# Connector-Section.net
KiCad netlist of a schematic drawn in Altium Designer
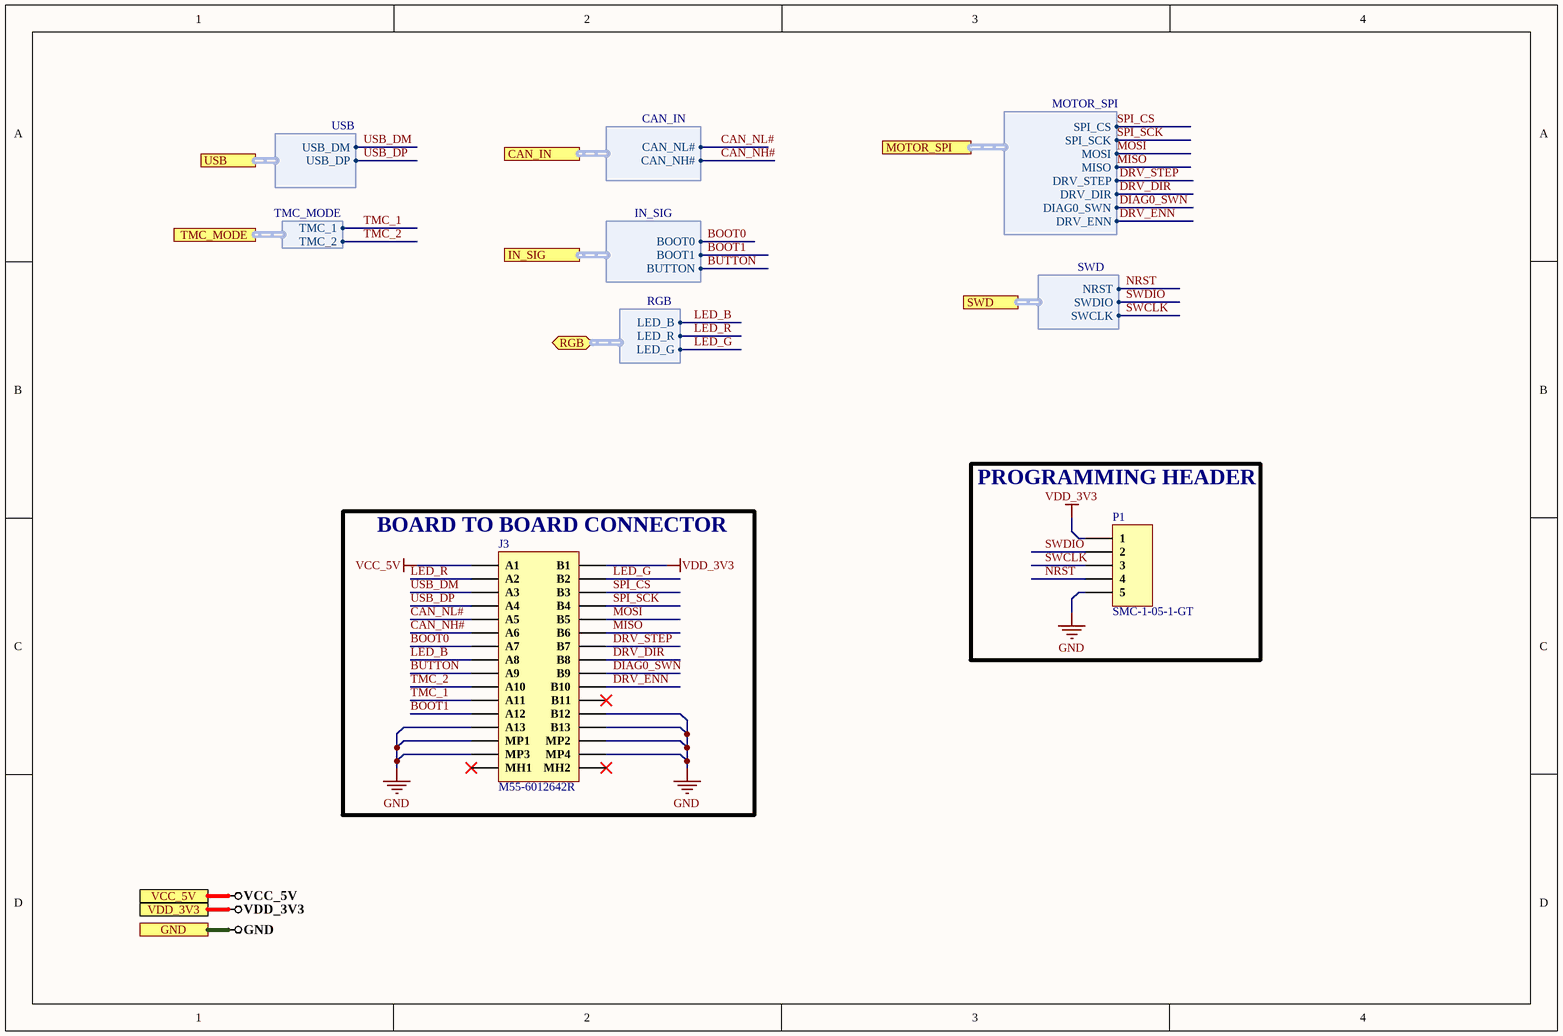
[diagram p0: Connector-Section.SchDoc]

(export (version "E")
  (design (tool "Eeschema 10.0.6"))
  (components
    (comp (ref "J3")
      (value "M55-6012642R")
      (footprint "M55-6012642R")
      (description "CONN RCPT 26POS 0.05 GOLD SMD")
      (fields (field (name "MANUFACTURER") "Harwin"))
      (libsource (lib "Cole_Benson") (part "M55-6012642R"))
    )
    (comp (ref "P1")
      (value "SMC-1-05-1-GT")
      (footprint "SMC-1-05-1-GT")
      (description "MACHINE PIN SOCKET 5P 2.54MM PIT")
      (fields (field (name "MANUFACTURER") "Adam Equipment"))
      (libsource (lib "Cole_Benson") (part "SMC-1-05-1-GT"))
    )
  )
  (nets
    (net (code "8") (name "/BOOT0") (class "Default")
      (node (ref "J3") (pin "A7") (pinfunction "A7_A7") (pintype "passive"))
    )
    (net (code "9") (name "/BOOT1") (class "Default")
      (node (ref "J3") (pin "A12") (pinfunction "A12_A12") (pintype "passive"))
    )
    (net (code "10") (name "/BUTTON") (class "Default")
      (node (ref "J3") (pin "A9") (pinfunction "A9_A9") (pintype "passive"))
    )
    (net (code "11") (name "/CAN_NH#") (class "Default")
      (node (ref "J3") (pin "A6") (pinfunction "A6_A6") (pintype "passive"))
    )
    (net (code "12") (name "/CAN_NL#") (class "Default")
      (node (ref "J3") (pin "A5") (pinfunction "A5_A5") (pintype "passive"))
    )
    (net (code "13") (name "/DIAG0_SWN") (class "Default")
      (node (ref "J3") (pin "B9") (pinfunction "B9_B9") (pintype "passive"))
    )
    (net (code "14") (name "/DRV_DIR") (class "Default")
      (node (ref "J3") (pin "B8") (pinfunction "B8_B8") (pintype "passive"))
    )
    (net (code "15") (name "/DRV_ENN") (class "Default")
      (node (ref "J3") (pin "B10") (pinfunction "B10_B10") (pintype "passive"))
    )
    (net (code "16") (name "/DRV_STEP") (class "Default")
      (node (ref "J3") (pin "B7") (pinfunction "B7_B7") (pintype "passive"))
    )
    (net (code "17") (name "/LED_B") (class "Default")
      (node (ref "J3") (pin "A8") (pinfunction "A8_A8") (pintype "passive"))
    )
    (net (code "18") (name "/LED_G") (class "Default")
      (node (ref "J3") (pin "B2") (pinfunction "B2_B2") (pintype "passive"))
    )
    (net (code "19") (name "/LED_R") (class "Default")
      (node (ref "J3") (pin "A2") (pinfunction "A2_A2") (pintype "passive"))
    )
    (net (code "20") (name "/MISO") (class "Default")
      (node (ref "J3") (pin "B6") (pinfunction "B6_B6") (pintype "passive"))
    )
    (net (code "21") (name "/MOSI") (class "Default")
      (node (ref "J3") (pin "B5") (pinfunction "B5_B5") (pintype "passive"))
    )
    (net (code "22") (name "/NRST") (class "Default")
      (node (ref "P1") (pin "4") (pinfunction "4_4") (pintype "passive"))
    )
    (net (code "23") (name "/SPI_CS") (class "Default")
      (node (ref "J3") (pin "B3") (pinfunction "B3_B3") (pintype "passive"))
    )
    (net (code "24") (name "/SPI_SCK") (class "Default")
      (node (ref "J3") (pin "B4") (pinfunction "B4_B4") (pintype "passive"))
    )
    (net (code "25") (name "/SWCLK") (class "Default")
      (node (ref "P1") (pin "3") (pinfunction "3_3") (pintype "passive"))
    )
    (net (code "26") (name "/SWDIO") (class "Default")
      (node (ref "P1") (pin "2") (pinfunction "2_2") (pintype "passive"))
    )
    (net (code "27") (name "/TMC_1") (class "Default")
      (node (ref "J3") (pin "A11") (pinfunction "A11_A11") (pintype "passive"))
    )
    (net (code "28") (name "/TMC_2") (class "Default")
      (node (ref "J3") (pin "A10") (pinfunction "A10_A10") (pintype "passive"))
    )
    (net (code "29") (name "/USB_DM") (class "Default")
      (node (ref "J3") (pin "A3") (pinfunction "A3_A3") (pintype "passive"))
    )
    (net (code "30") (name "/USB_DP") (class "Default")
      (node (ref "J3") (pin "A4") (pinfunction "A4_A4") (pintype "passive"))
    )
    (net (code "38") (name "GND") (class "Default")
      (node (ref "J3") (pin "A13") (pinfunction "A13_A13") (pintype "passive"))
      (node (ref "J3") (pin "B12") (pinfunction "B12_B12") (pintype "passive"))
      (node (ref "J3") (pin "B13") (pinfunction "B13_B13") (pintype "passive"))
      (node (ref "J3") (pin "MP1") (pinfunction "MP1_MP1") (pintype "passive"))
      (node (ref "J3") (pin "MP2") (pinfunction "MP2_MP2") (pintype "passive"))
      (node (ref "J3") (pin "MP3") (pinfunction "MP3_MP3") (pintype "passive"))
      (node (ref "J3") (pin "MP4") (pinfunction "MP4_MP4") (pintype "passive"))
      (node (ref "P1") (pin "5") (pinfunction "5_5") (pintype "passive"))
    )
    (net (code "39") (name "VCC_5V") (class "Default")
      (node (ref "J3") (pin "A1") (pinfunction "A1_A1") (pintype "passive"))
    )
    (net (code "40") (name "VDD_3V3") (class "Default")
      (node (ref "J3") (pin "B1") (pinfunction "B1_B1") (pintype "passive"))
      (node (ref "P1") (pin "1") (pinfunction "1_1") (pintype "passive"))
    )
    (net (code "41") (name "unconnected-(J3-PadB11)") (class "Default")
      (node (ref "J3") (pin "B11") (pinfunction "B11_B11") (pintype "passive+no_connect"))
    )
    (net (code "42") (name "unconnected-(J3-PadMH1)") (class "Default")
      (node (ref "J3") (pin "MH1") (pinfunction "MH1_MH1") (pintype "passive+no_connect"))
    )
    (net (code "43") (name "unconnected-(J3-PadMH2)") (class "Default")
      (node (ref "J3") (pin "MH2") (pinfunction "MH2_MH2") (pintype "passive+no_connect"))
    )
  )
)
